# OpenRing_MCU.net
KiCad netlist of a schematic drawn in Altium Designer
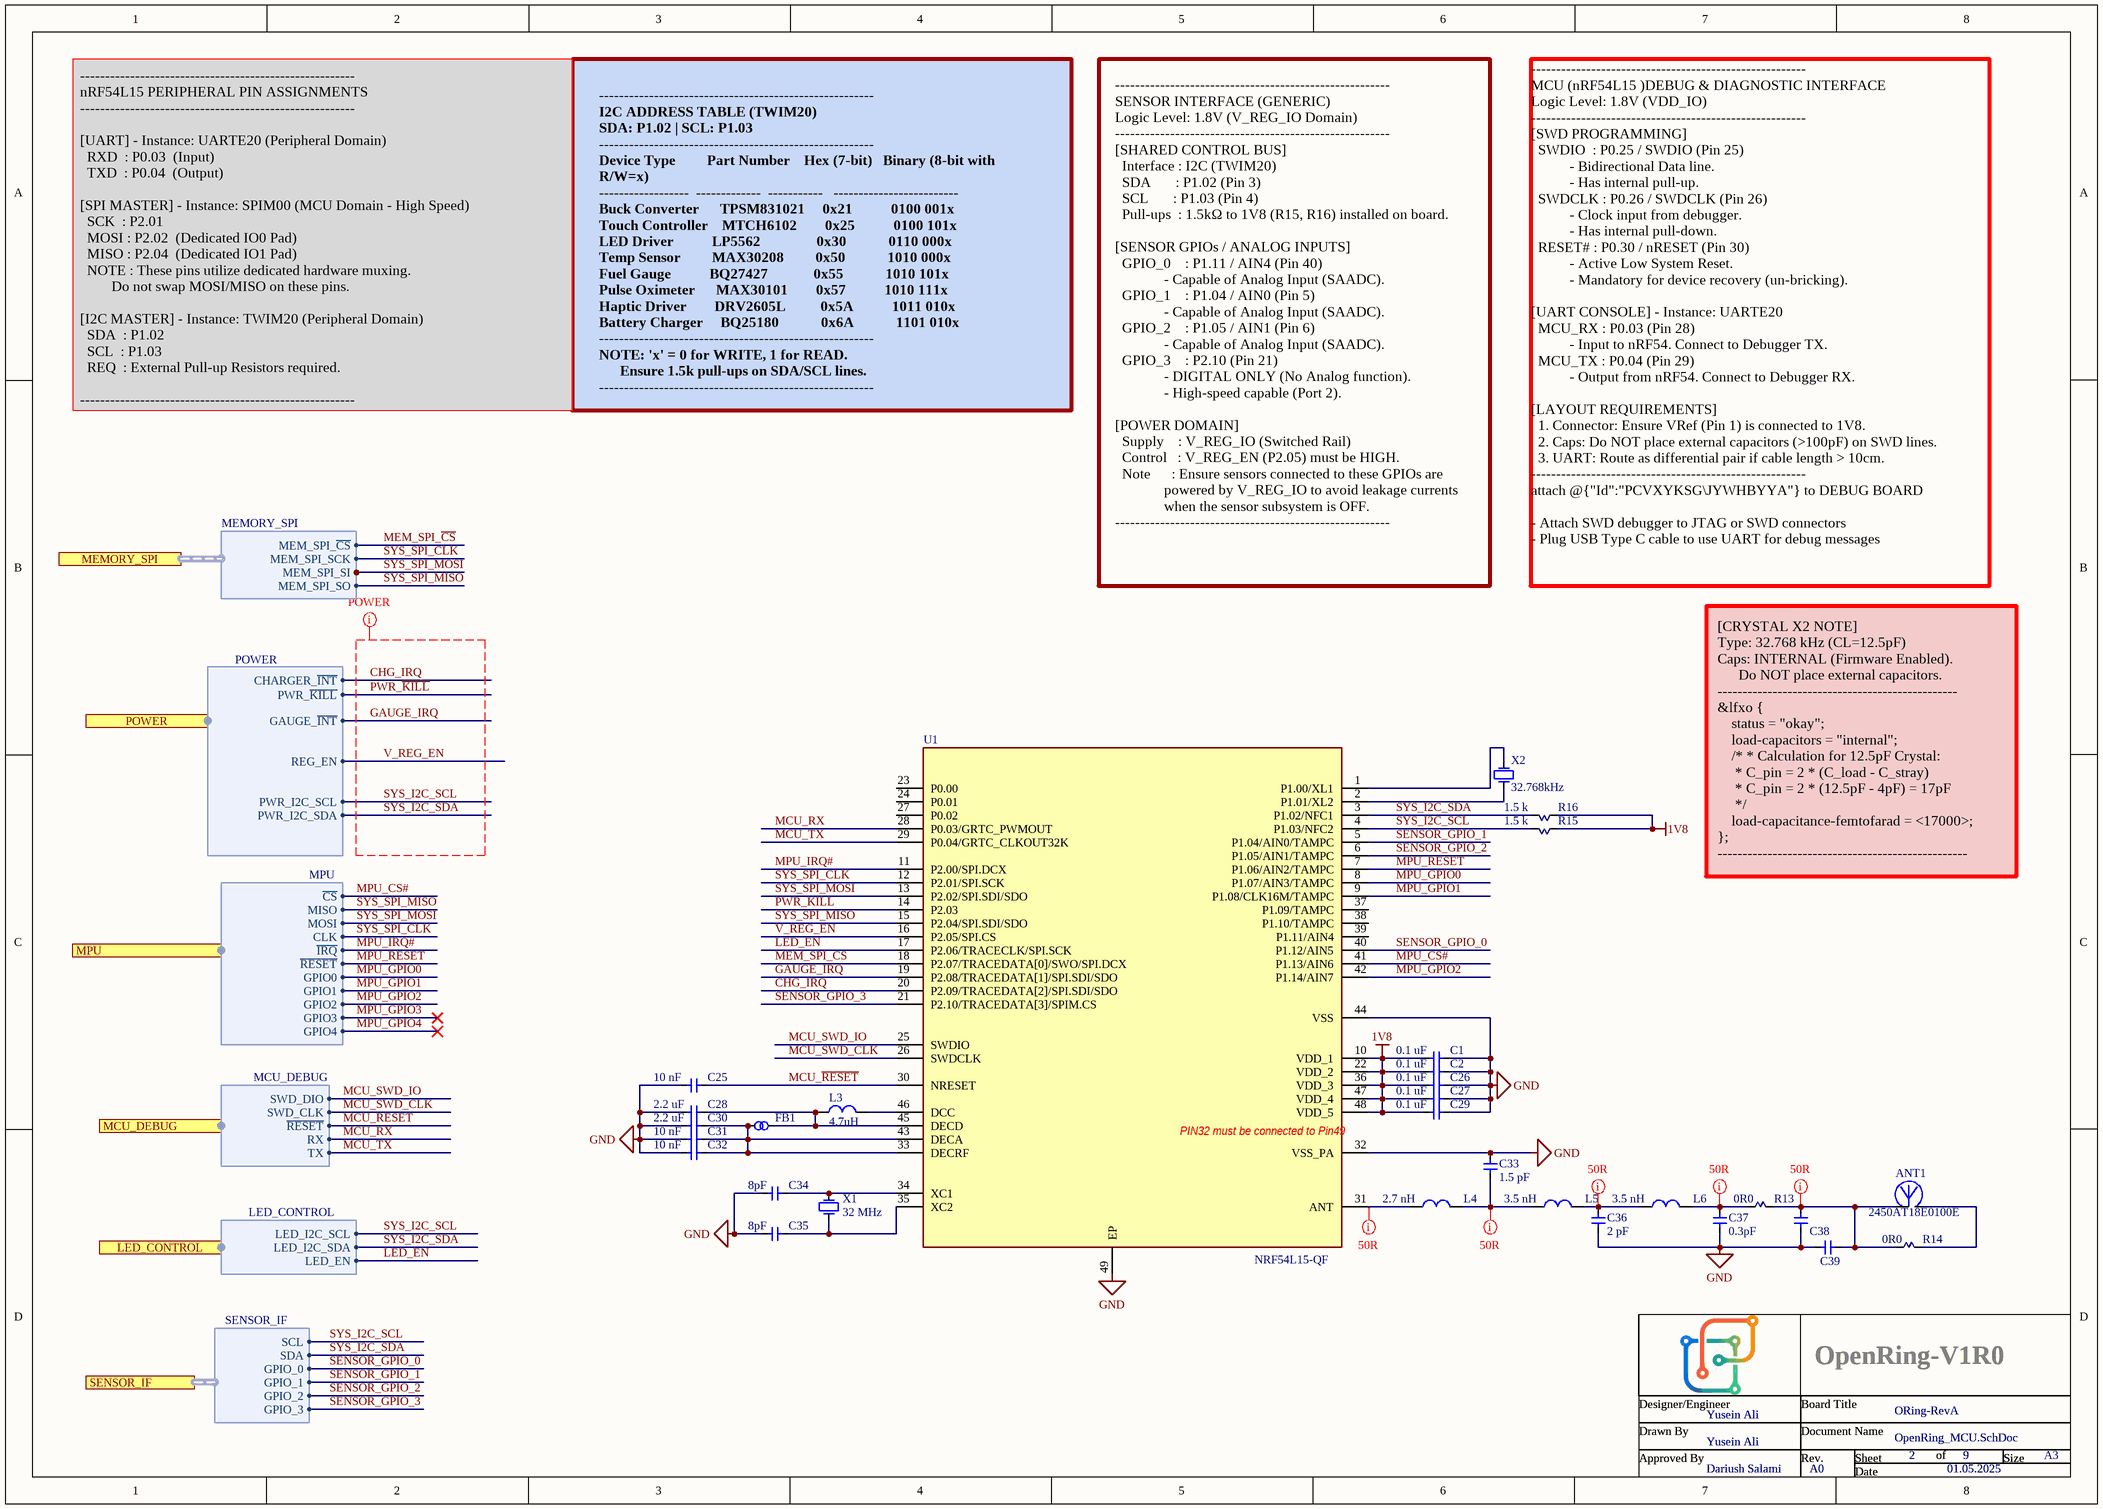
[diagram p0: OpenRing_MCU.SchDoc]

(export (version "E")
  (design (tool "Eeschema 10.0.6"))
  (components
    (comp (ref "ANT1")
      (value "2450AT18E0100E")
      (footprint "ANTC3216X130N")
      (description "7 Inch Reel / Mini 2.45Ghz Chip Antenna")
      (fields (field (name "MANUFACTURER") "Johanson") (field (name "CHECKED") "TRUE"))
      (libsource (lib "RFComponents") (part "2450AT18E0100E"))
    )
    (comp (ref "C1")
      (value "0.1 uF")
      (footprint "CAPC1005X05N")
      (description "CAP CER 0.1UF 16V X5R 0402")
      (fields
        (field (name "MANUFACTURER") "Murata Electronics")
        (field (name "MANUFACTURER PART NUMBER") "GRM155R61C104KA88D")
      )
      (libsource (lib "OpenRingComponents") (part "GRM155R61C104KA88D"))
    )
    (comp (ref "C2")
      (value "0.1 uF")
      (footprint "CAPC1005X05N")
      (description "CAP CER 0.1UF 16V X5R 0402")
      (fields
        (field (name "MANUFACTURER") "Murata Electronics")
        (field (name "MANUFACTURER PART NUMBER") "GRM155R61C104KA88D")
      )
      (libsource (lib "OpenRingComponents") (part "GRM155R61C104KA88D"))
    )
    (comp (ref "C25")
      (value "10 nF")
      (footprint "CAPC1005X05N")
      (description "CAP CER 10000PF 50V X7R 0402")
      (fields
        (field (name "MANUFACTURER") "Murata Electronics North America")
        (field (name "MANUFACTURER PART NUMBER") "GRM155R71H103KA88D")
      )
      (libsource (lib "OpenRingComponents") (part "GRM155R71H103KA88D"))
    )
    (comp (ref "C26")
      (value "0.1 uF")
      (footprint "CAPC1005X05N")
      (description "CAP CER 0.1UF 16V X5R 0402")
      (fields
        (field (name "MANUFACTURER") "Murata Electronics")
        (field (name "MANUFACTURER PART NUMBER") "GRM155R61C104KA88D")
      )
      (libsource (lib "OpenRingComponents") (part "GRM155R61C104KA88D"))
    )
    (comp (ref "C27")
      (value "0.1 uF")
      (footprint "CAPC1005X05N")
      (description "CAP CER 0.1UF 16V X5R 0402")
      (fields
        (field (name "MANUFACTURER") "Murata Electronics")
        (field (name "MANUFACTURER PART NUMBER") "GRM155R61C104KA88D")
      )
      (libsource (lib "OpenRingComponents") (part "GRM155R61C104KA88D"))
    )
    (comp (ref "C28")
      (value "2.2 uF")
      (footprint "CAPC1005X05N")
      (description "CAP CER 2.2UF 10V X5R 0402")
      (fields
        (field (name "MANUFACTURER") "Murata Electronics North America")
        (field (name "MANUFACTURER PART NUMBER") "GRM155R61A225KE95D")
      )
      (libsource (lib "OpenRingComponents") (part "GRM155R61A225KE95D"))
    )
    (comp (ref "C29")
      (value "0.1 uF")
      (footprint "CAPC1005X05N")
      (description "CAP CER 0.1UF 16V X5R 0402")
      (fields
        (field (name "MANUFACTURER") "Murata Electronics")
        (field (name "MANUFACTURER PART NUMBER") "GRM155R61C104KA88D")
      )
      (libsource (lib "OpenRingComponents") (part "GRM155R61C104KA88D"))
    )
    (comp (ref "C30")
      (value "2.2 uF")
      (footprint "CAPC1005X05N")
      (description "CAP CER 2.2UF 10V X5R 0402")
      (fields
        (field (name "MANUFACTURER") "Murata Electronics North America")
        (field (name "MANUFACTURER PART NUMBER") "GRM155R61A225KE95D")
      )
      (libsource (lib "OpenRingComponents") (part "GRM155R61A225KE95D"))
    )
    (comp (ref "C31")
      (value "10 nF")
      (footprint "CAPC1005X05N")
      (description "CAP CER 10000PF 50V X7R 0402")
      (fields
        (field (name "MANUFACTURER") "Murata Electronics North America")
        (field (name "MANUFACTURER PART NUMBER") "GRM155R71H103KA88D")
      )
      (libsource (lib "OpenRingComponents") (part "GRM155R71H103KA88D"))
    )
    (comp (ref "C32")
      (value "10 nF")
      (footprint "CAPC1005X05N")
      (description "CAP CER 10000PF 50V X7R 0402")
      (fields
        (field (name "MANUFACTURER") "Murata Electronics North America")
        (field (name "MANUFACTURER PART NUMBER") "GRM155R71H103KA88D")
      )
      (libsource (lib "OpenRingComponents") (part "GRM155R71H103KA88D"))
    )
    (comp (ref "C33")
      (value "1.5 pF")
      (footprint "CAPC1005X05N")
      (description "Multilayer Ceramic Capacitor, 1.5 pF, 50 V, ï¿½ 0.1pF, C0G (NP0), 0402 [1005 Metric]")
      (fields
        (field (name "MANUFACTURER") "Murata")
        (field (name "MANUFACTURER PART NUMBER") "GJM1555C1H1R5BB01D")
      )
      (libsource (lib "OpenRingComponents") (part "GJM1555C1H1R5BB01D"))
    )
    (comp (ref "C34")
      (value "8pF")
      (footprint "CAPC1005X05N")
      (description "Multilayer Ceramic Capacitors MLCC - SMD/SMT 0402 8.0pF 50volts C0G +/-0.05pF")
      (fields
        (field (name "MANUFACTURER") "Murata")
        (field (name "MANUFACTURER PART NUMBER") "GRM1555C1H8R0BA01D")
      )
      (libsource (lib "OpenRingComponents") (part "GRM1555C1H8R0BA01D"))
    )
    (comp (ref "C35")
      (value "8pF")
      (footprint "CAPC1005X05N")
      (description "Multilayer Ceramic Capacitors MLCC - SMD/SMT 0402 8.0pF 50volts C0G +/-0.05pF")
      (fields
        (field (name "MANUFACTURER") "Murata")
        (field (name "MANUFACTURER PART NUMBER") "GRM1555C1H8R0BA01D")
      )
      (libsource (lib "OpenRingComponents") (part "GRM1555C1H8R0BA01D"))
    )
    (comp (ref "C36")
      (value "2 pF")
      (footprint "CAPC1005X05N")
      (description "0402 2 pF 50V ±0.05 pF Tolerance C0G SMT Multilayer Ceramic Capacitor")
      (fields
        (field (name "MANUFACTURER") "Murata")
        (field (name "MANUFACTURER PART NUMBER") "GJM1555C1H2R0WB01D")
      )
      (libsource (lib "Passives") (part "GJM1555C1H2R0WB01D"))
    )
    (comp (ref "C37")
      (value "0.3pF")
      (footprint "INDC1005X06N")
      (description "0402 0.3 pF 50V ±0.05 pF Tolerance C0G SMT Multilayer Ceramic Capacitor")
      (fields
        (field (name "MANUFACTURER") "Murata")
        (field (name "MANUFACTURER PART NUMBER") "GJM1555C1HR30WB01D")
      )
      (libsource (lib "OpenRingComponents") (part "GJM1555C1HR30WB01D"))
    )
    (comp (ref "C38")
      (value "NC")
      (footprint "CAPC1005X05N")
      (libsource (lib "OpenRingComponents") (part "CAPACITOR"))
    )
    (comp (ref "C39")
      (value "NC")
      (footprint "CAPC1005X05N")
      (libsource (lib "OpenRingComponents") (part "CAPACITOR"))
    )
    (comp (ref "FB1")
      (value "BLM15AG121SN1D")
      (footprint "INDC1005X06N")
      (description "Ferrite Beads Multi-Layer 120Ohm 25% 100MHz 550mA 190mOhm DCR 0402 Paper T/R")
      (fields (field (name "MANUFACTURER") "Murata") (field (name "TOLERANCE") "25%"))
      (libsource (lib "OpenRingComponents") (part "BLM15AG121SN1D"))
    )
    (comp (ref "L3")
      (value "4.7uH")
      (footprint "INDC1005X06N")
      (description "Inductor Power Chip Shielded Multi-Layer 4.7uH 20% 1MHz Ferrite 0.08A 0.78Ohm DCR 0603 T/R")
      (fields
        (field (name "MANUFACTURER") "Murata")
        (field (name "MANUFACTURER PART NUMBER") "LQM18FN4R7M00D")
      )
      (libsource (lib "Passives") (part "LQM18FN4R7M00D"))
    )
    (comp (ref "L4")
      (value "2.7 nH")
      (footprint "INDC1005X06N")
      (description "Inductor Chip 2.7nH 0.1nH Tolerance 2-Pin 0402 Paper T/R")
      (fields
        (field (name "MANUFACTURER") "Murata")
        (field (name "MANUFACTURER PART NUMBER") "LQG15WH2N7B02D")
      )
      (libsource (lib "OpenRingComponents") (part "LQG15WH2N7B02D"))
    )
    (comp (ref "L5")
      (value "3.5 nH")
      (footprint "INDC1005X06N")
      (description "Inductor Chip 3.5nH 0.1nH Tolerance 2-Pin 0402 Paper T/R")
      (fields
        (field (name "MANUFACTURER") "Murata")
        (field (name "MANUFACTURER PART NUMBER") "LQG15WH3N5B02D")
      )
      (libsource (lib "OpenRingComponents") (part "LQG15WH3N5B02D"))
    )
    (comp (ref "L6")
      (value "3.5 nH")
      (footprint "INDC1005X06N")
      (description "Inductor Chip 3.5nH 0.1nH Tolerance 2-Pin 0402 Paper T/R")
      (fields
        (field (name "MANUFACTURER") "Murata")
        (field (name "MANUFACTURER PART NUMBER") "LQG15WH3N5B02D")
      )
      (libsource (lib "OpenRingComponents") (part "LQG15WH3N5B02D"))
    )
    (comp (ref "R13")
      (value "0R0")
      (footprint "RESC1005X04N")
      (description "RES SMD 0.0OHM JUMPER 1/10W 0402")
      (fields
        (field (name "MANUFACTURER") "Panasonic Electronic Components")
        (field (name "MANUFACTURER PART NUMBER") "ERJ-2GE0R00X")
      )
      (libsource (lib "OpenRingComponents") (part "ERJ-2GE0R00X"))
    )
    (comp (ref "R14")
      (value "0R0")
      (footprint "RESC1005X04N")
      (description "RES SMD 0.0OHM JUMPER 1/10W 0402")
      (fields
        (field (name "MANUFACTURER") "Panasonic Electronic Components")
        (field (name "MANUFACTURER PART NUMBER") "ERJ-2GE0R00X")
      )
      (libsource (lib "OpenRingComponents") (part "ERJ-2GE0R00X"))
    )
    (comp (ref "R15")
      (value "1.5 k")
      (footprint "RESC1005X04N")
      (description "RES SMD 1.5K OHM 1% 1/10W 0402")
      (fields
        (field (name "MANUFACTURER") "Panasonic Electronic Components")
        (field (name "MANUFACTURER PART NUMBER") "ERJ-2RKF1501X")
      )
      (libsource (lib "OpenRingComponents") (part "ERJ-2RKF1501X"))
    )
    (comp (ref "R16")
      (value "1.5 k")
      (footprint "RESC1005X04N")
      (description "RES SMD 1.5K OHM 1% 1/10W 0402")
      (fields
        (field (name "MANUFACTURER") "Panasonic Electronic Components")
        (field (name "MANUFACTURER PART NUMBER") "ERJ-2RKF1501X")
      )
      (libsource (lib "OpenRingComponents") (part "ERJ-2RKF1501X"))
    )
    (comp (ref "U1")
      (value "NRF54L15-QF")
      (footprint "QFN40P600X600X95-49N")
      (description "nRF54L15 SoC with Arm Cortex-M33 processor")
      (fields
        (field (name "MANUFACTURER") "Nordic Semiconductor")
        (field (name "MANUFACTURER PART NUMBER") "NRF54L15-QFAA-R")
      )
      (libsource (lib "OpenRingComponents") (part "NRF54L15-QFAA-R"))
    )
    (comp (ref "X1")
      (value "32 MHz")
      (footprint "FP-ABM11W-MFG")
      (description "CRYSTAL 32.0000MHZ 8PF SMD, 2x1.6mm, RoHS")
      (fields
        (field (name "MANUFACTURER") "Abracon")
        (field (name "MANUFACTURER PART NUMBER") "ABM11W-32.0000MHZ-8-B1U-T3")
        (field (name "CHECKED") "TRUE")
      )
      (libsource (lib "Passives") (part "ABM11W-32.0000MHZ-8-B1U-T3"))
    )
    (comp (ref "X2")
      (value "32.768kHz")
      (footprint "Abracon_ABS6_2012X06L")
      (description "CRYSTAL 32.768 KHZ 12.5 PF SMD")
      (fields
        (field (name "MANUFACTURER") "Abracon Corporation")
        (field (name "MANUFACTURER PART NUMBER") "ABS06-32.768KHZ-1-T")
      )
      (libsource (lib "OpenRingComponents") (part "ABS06-32.768KHZ-1-T"))
    )
  )
  (nets
    (net (code "7") (name "/CHG_IRQ") (class "Default")
      (node (ref "U1") (pin "20") (pinfunction "P2.09/TRACEDATA[2]/SPI.SDI/SDO_20") (pintype "passive"))
    )
    (net (code "8") (name "/GAUGE_IRQ") (class "Default")
      (node (ref "U1") (pin "19") (pinfunction "P2.08/TRACEDATA[1]/SPI.SDI/SDO_19") (pintype "passive"))
    )
    (net (code "9") (name "/LED_EN") (class "Default")
      (node (ref "U1") (pin "17") (pinfunction "P2.06/TRACECLK/SPI.SCK_17") (pintype "passive"))
    )
    (net (code "10") (name "/MCU_RX") (class "Default")
      (node (ref "U1") (pin "28") (pinfunction "P0.03/GRTC_PWMOUT_28") (pintype "passive"))
    )
    (net (code "11") (name "/MCU_SWD_CLK") (class "Default")
      (node (ref "U1") (pin "26") (pinfunction "SWDCLK_26") (pintype "passive"))
    )
    (net (code "12") (name "/MCU_SWD_IO") (class "Default")
      (node (ref "U1") (pin "25") (pinfunction "SWDIO_25") (pintype "passive"))
    )
    (net (code "13") (name "/MCU_TX") (class "Default")
      (node (ref "U1") (pin "29") (pinfunction "P0.04/GRTC_CLKOUT32K_29") (pintype "passive"))
    )
    (net (code "14") (name "/MCU_~{RESET}") (class "Default")
      (node (ref "C25") (pin "2") (pinfunction "2_2") (pintype "passive"))
      (node (ref "U1") (pin "30") (pinfunction "NRESET_30") (pintype "passive"))
    )
    (net (code "15") (name "/MEM_SPI_~{CS}") (class "Default")
      (node (ref "U1") (pin "18") (pinfunction "P2.07/TRACEDATA[0]/SWO/SPI.DCX_18") (pintype "passive"))
    )
    (net (code "16") (name "/MPU_CS#") (class "Default")
      (node (ref "U1") (pin "41") (pinfunction "P1.13/AIN6_41") (pintype "passive"))
    )
    (net (code "17") (name "/MPU_GPIO0") (class "Default")
      (node (ref "U1") (pin "8") (pinfunction "P1.07/AIN3/TAMPC_8") (pintype "passive"))
    )
    (net (code "18") (name "/MPU_GPIO1") (class "Default")
      (node (ref "U1") (pin "9") (pinfunction "P1.08/CLK16M/TAMPC_9") (pintype "passive"))
    )
    (net (code "19") (name "/MPU_GPIO2") (class "Default")
      (node (ref "U1") (pin "42") (pinfunction "P1.14/AIN7_42") (pintype "passive"))
    )
    (net (code "22") (name "/MPU_IRQ#") (class "Default")
      (node (ref "U1") (pin "11") (pinfunction "P2.00/SPI.DCX_11") (pintype "passive"))
    )
    (net (code "23") (name "/MPU_~{RESET}") (class "Default")
      (node (ref "U1") (pin "7") (pinfunction "P1.06/AIN2/TAMPC_7") (pintype "passive"))
    )
    (net (code "24") (name "/PWR_~{KILL}") (class "Default")
      (node (ref "U1") (pin "14") (pinfunction "P2.03_14") (pintype "passive"))
    )
    (net (code "25") (name "/SENSOR_GPIO_0") (class "Default")
      (node (ref "U1") (pin "40") (pinfunction "P1.12/AIN5_40") (pintype "passive"))
    )
    (net (code "26") (name "/SENSOR_GPIO_1") (class "Default")
      (node (ref "U1") (pin "5") (pinfunction "P1.04/AIN0/TAMPC_5") (pintype "passive"))
    )
    (net (code "27") (name "/SENSOR_GPIO_2") (class "Default")
      (node (ref "U1") (pin "6") (pinfunction "P1.05/AIN1/TAMPC_6") (pintype "passive"))
    )
    (net (code "28") (name "/SENSOR_GPIO_3") (class "Default")
      (node (ref "U1") (pin "21") (pinfunction "P2.10/TRACEDATA[3]/SPIM.CS_21") (pintype "passive"))
    )
    (net (code "29") (name "/SYS_I2C_SCL") (class "Default")
      (node (ref "R15") (pin "2") (pinfunction "2_2") (pintype "passive"))
      (node (ref "U1") (pin "4") (pinfunction "P1.03/NFC2_4") (pintype "passive"))
    )
    (net (code "30") (name "/SYS_I2C_SDA") (class "Default")
      (node (ref "R16") (pin "2") (pinfunction "2_2") (pintype "passive"))
      (node (ref "U1") (pin "3") (pinfunction "P1.02/NFC1_3") (pintype "passive"))
    )
    (net (code "31") (name "/SYS_SPI_CLK") (class "Default")
      (node (ref "U1") (pin "12") (pinfunction "P2.01/SPI.SCK_12") (pintype "passive"))
    )
    (net (code "32") (name "/SYS_SPI_MISO") (class "Default")
      (node (ref "U1") (pin "15") (pinfunction "P2.04/SPI.SDI/SDO_15") (pintype "passive"))
    )
    (net (code "33") (name "/SYS_SPI_MOSI") (class "Default")
      (node (ref "U1") (pin "13") (pinfunction "P2.02/SPI.SDI/SDO_13") (pintype "passive"))
    )
    (net (code "34") (name "/V_REG_EN") (class "Default")
      (node (ref "U1") (pin "16") (pinfunction "P2.05/SPI.CS_16") (pintype "passive"))
    )
    (net (code "41") (name "1V8") (class "Default")
      (node (ref "C1") (pin "1") (pinfunction "1_1") (pintype "passive"))
      (node (ref "C2") (pin "1") (pinfunction "1_1") (pintype "passive"))
      (node (ref "C26") (pin "1") (pinfunction "1_1") (pintype "passive"))
      (node (ref "C27") (pin "1") (pinfunction "1_1") (pintype "passive"))
      (node (ref "C29") (pin "1") (pinfunction "1_1") (pintype "passive"))
      (node (ref "R15") (pin "1") (pinfunction "1_1") (pintype "passive"))
      (node (ref "R16") (pin "1") (pinfunction "1_1") (pintype "passive"))
      (node (ref "U1") (pin "10") (pinfunction "VDD_1_10") (pintype "passive"))
      (node (ref "U1") (pin "22") (pinfunction "VDD_2_22") (pintype "passive"))
      (node (ref "U1") (pin "36") (pinfunction "VDD_3_36") (pintype "passive"))
      (node (ref "U1") (pin "47") (pinfunction "VDD_4_47") (pintype "passive"))
      (node (ref "U1") (pin "48") (pinfunction "VDD_5_48") (pintype "passive"))
    )
    (net (code "42") (name "GND") (class "Default")
      (node (ref "C1") (pin "2") (pinfunction "2_2") (pintype "passive"))
      (node (ref "C2") (pin "2") (pinfunction "2_2") (pintype "passive"))
      (node (ref "C25") (pin "1") (pinfunction "1_1") (pintype "passive"))
      (node (ref "C26") (pin "2") (pinfunction "2_2") (pintype "passive"))
      (node (ref "C27") (pin "2") (pinfunction "2_2") (pintype "passive"))
      (node (ref "C28") (pin "1") (pinfunction "1_1") (pintype "passive"))
      (node (ref "C29") (pin "2") (pinfunction "2_2") (pintype "passive"))
      (node (ref "C30") (pin "1") (pinfunction "1_1") (pintype "passive"))
      (node (ref "C31") (pin "1") (pinfunction "1_1") (pintype "passive"))
      (node (ref "C32") (pin "1") (pinfunction "1_1") (pintype "passive"))
      (node (ref "C33") (pin "2") (pinfunction "2_2") (pintype "passive"))
      (node (ref "C34") (pin "1") (pinfunction "1_1") (pintype "passive"))
      (node (ref "C35") (pin "1") (pinfunction "1_1") (pintype "passive"))
      (node (ref "C36") (pin "1") (pinfunction "1_1") (pintype "passive"))
      (node (ref "C37") (pin "1") (pinfunction "1_1") (pintype "passive"))
      (node (ref "C38") (pin "1") (pinfunction "1_1") (pintype "passive"))
      (node (ref "C39") (pin "2") (pinfunction "2_2") (pintype "passive"))
      (node (ref "U1") (pin "32") (pinfunction "VSS_PA_32") (pintype "passive"))
      (node (ref "U1") (pin "44") (pinfunction "VSS_44") (pintype "passive"))
      (node (ref "U1") (pin "49") (pinfunction "EP_49") (pintype "passive"))
    )
    (net (code "43") (name "Net-(ANT1-Pad1)") (class "Default")
      (node (ref "ANT1") (pin "1") (pinfunction "1_1") (pintype "passive"))
      (node (ref "C38") (pin "2") (pinfunction "2_2") (pintype "passive"))
      (node (ref "C39") (pin "1") (pinfunction "1_1") (pintype "passive"))
      (node (ref "R13") (pin "2") (pinfunction "2_2") (pintype "passive"))
      (node (ref "R14") (pin "1") (pinfunction "1_1") (pintype "passive"))
    )
    (net (code "44") (name "Net-(ANT1-Pad2)") (class "Default")
      (node (ref "ANT1") (pin "2") (pinfunction "2_2") (pintype "passive"))
      (node (ref "R14") (pin "2") (pinfunction "2_2") (pintype "passive"))
    )
    (net (code "45") (name "Net-(C33-Pad1)") (class "Default")
      (node (ref "C33") (pin "1") (pinfunction "1_1") (pintype "passive"))
      (node (ref "L4") (pin "2") (pinfunction "2_2") (pintype "passive"))
      (node (ref "L5") (pin "1") (pinfunction "1_1") (pintype "passive"))
    )
    (net (code "46") (name "Net-(C36-Pad2)") (class "Default")
      (node (ref "C36") (pin "2") (pinfunction "2_2") (pintype "passive"))
      (node (ref "L5") (pin "2") (pinfunction "2_2") (pintype "passive"))
      (node (ref "L6") (pin "1") (pinfunction "1_1") (pintype "passive"))
    )
    (net (code "47") (name "Net-(C37-Pad2)") (class "Default")
      (node (ref "C37") (pin "2") (pinfunction "2_2") (pintype "passive"))
      (node (ref "L6") (pin "2") (pinfunction "2_2") (pintype "passive"))
      (node (ref "R13") (pin "1") (pinfunction "1_1") (pintype "passive"))
    )
    (net (code "48") (name "Net-(U1-ANT)") (class "Default")
      (node (ref "L4") (pin "1") (pinfunction "1_1") (pintype "passive"))
      (node (ref "U1") (pin "31") (pinfunction "ANT_31") (pintype "passive"))
    )
    (net (code "49") (name "Net-(U1-DCC)") (class "Default")
      (node (ref "L3") (pin "2") (pinfunction "2_2") (pintype "passive"))
      (node (ref "U1") (pin "46") (pinfunction "DCC_46") (pintype "passive"))
    )
    (net (code "50") (name "Net-(U1-DECA)") (class "Default")
      (node (ref "C30") (pin "2") (pinfunction "2_2") (pintype "passive"))
      (node (ref "C31") (pin "2") (pinfunction "2_2") (pintype "passive"))
      (node (ref "C32") (pin "2") (pinfunction "2_2") (pintype "passive"))
      (node (ref "FB1") (pin "1") (pinfunction "1_1") (pintype "passive"))
      (node (ref "U1") (pin "33") (pinfunction "DECRF_33") (pintype "passive"))
      (node (ref "U1") (pin "43") (pinfunction "DECA_43") (pintype "passive"))
    )
    (net (code "51") (name "Net-(U1-DECD)") (class "Default")
      (node (ref "C28") (pin "2") (pinfunction "2_2") (pintype "passive"))
      (node (ref "FB1") (pin "2") (pinfunction "2_2") (pintype "passive"))
      (node (ref "L3") (pin "1") (pinfunction "1_1") (pintype "passive"))
      (node (ref "U1") (pin "45") (pinfunction "DECD_45") (pintype "passive"))
    )
    (net (code "52") (name "Net-(U1-P1.00{slash}XL1)") (class "Default")
      (node (ref "U1") (pin "1") (pinfunction "P1.00/XL1_1") (pintype "passive"))
      (node (ref "X2") (pin "2") (pinfunction "OSC2_2") (pintype "passive"))
    )
    (net (code "53") (name "Net-(U1-P1.01{slash}XL2)") (class "Default")
      (node (ref "U1") (pin "2") (pinfunction "P1.01/XL2_2") (pintype "passive"))
      (node (ref "X2") (pin "1") (pinfunction "OSC1_1") (pintype "passive"))
    )
    (net (code "54") (name "Net-(U1-XC1)") (class "Default")
      (node (ref "C34") (pin "2") (pinfunction "2_2") (pintype "passive"))
      (node (ref "U1") (pin "34") (pinfunction "XC1_34") (pintype "passive"))
      (node (ref "X1") (pin "3") (pinfunction "OSC2_3") (pintype "passive"))
    )
    (net (code "55") (name "Net-(U1-XC2)") (class "Default")
      (node (ref "C35") (pin "2") (pinfunction "2_2") (pintype "passive"))
      (node (ref "U1") (pin "35") (pinfunction "XC2_35") (pintype "passive"))
      (node (ref "X1") (pin "1") (pinfunction "OSC1_1") (pintype "passive"))
    )
    (net (code "56") (name "unconnected-(U1-P0.00-Pad23)") (class "Default")
      (node (ref "U1") (pin "23") (pinfunction "P0.00_23") (pintype "passive"))
    )
    (net (code "57") (name "unconnected-(U1-P0.01-Pad24)") (class "Default")
      (node (ref "U1") (pin "24") (pinfunction "P0.01_24") (pintype "passive"))
    )
    (net (code "58") (name "unconnected-(U1-P0.02-Pad27)") (class "Default")
      (node (ref "U1") (pin "27") (pinfunction "P0.02_27") (pintype "passive"))
    )
    (net (code "59") (name "unconnected-(U1-P1.09{slash}TAMPC-Pad37)") (class "Default")
      (node (ref "U1") (pin "37") (pinfunction "P1.09/TAMPC_37") (pintype "passive"))
    )
    (net (code "60") (name "unconnected-(U1-P1.10{slash}TAMPC-Pad38)") (class "Default")
      (node (ref "U1") (pin "38") (pinfunction "P1.10/TAMPC_38") (pintype "passive"))
    )
    (net (code "61") (name "unconnected-(U1-P1.11{slash}AIN4-Pad39)") (class "Default")
      (node (ref "U1") (pin "39") (pinfunction "P1.11/AIN4_39") (pintype "passive"))
    )
  )
)
